# XmegaA4U_v2_0.net
KiCad netlist of a schematic drawn in EAGLE
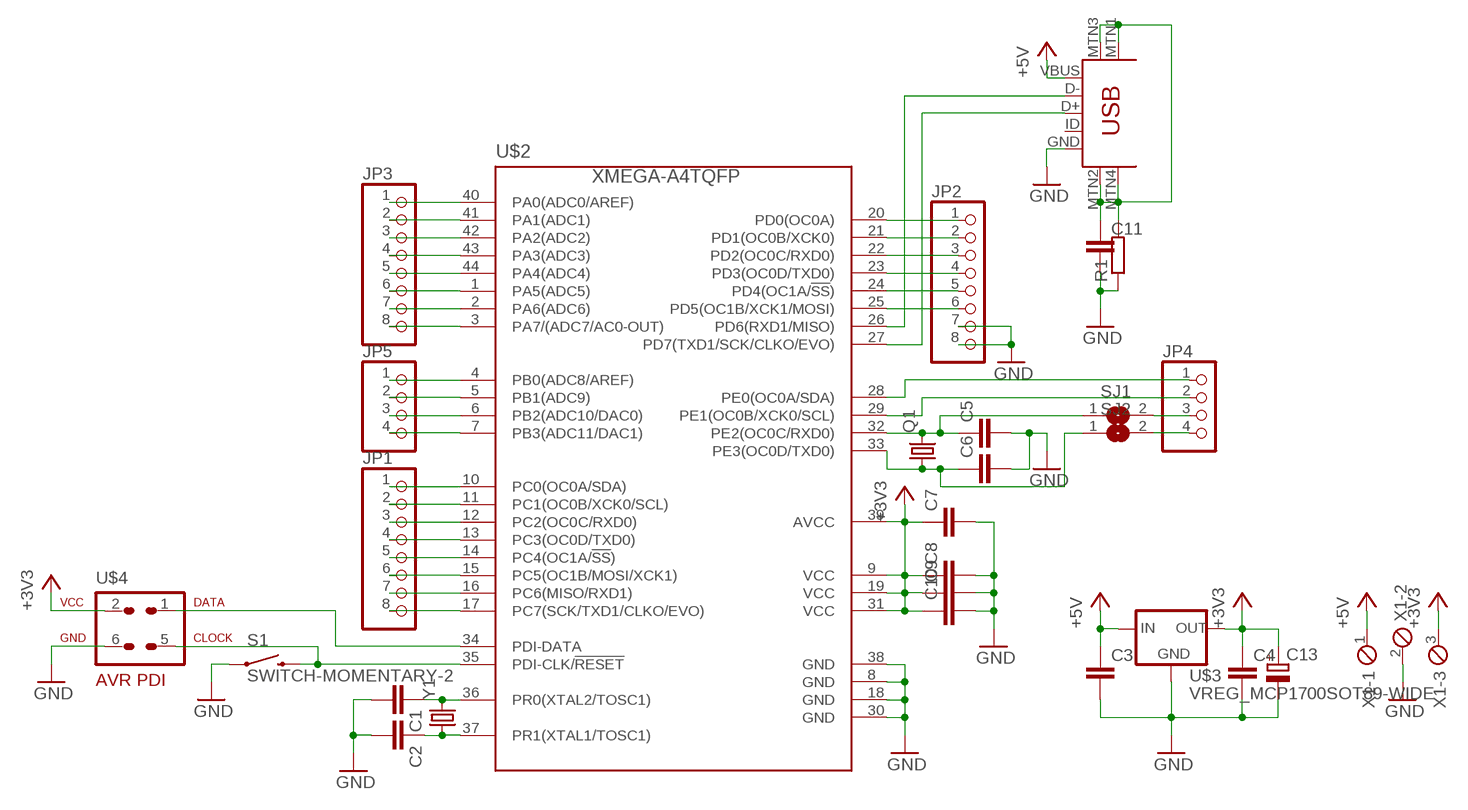
[diagram p0: schematic, sheet 1]

(export (version "E")
  (design (tool "Eeschema 10.0.6"))
  (components
    (comp (ref "C1")
      (value "C-EUC0603")
      (footprint "eagle-import:C0603")
      (libsource (lib "eagle-import") (part "C-EUC0603"))
    )
    (comp (ref "C2")
      (value "C-EUC0603")
      (footprint "eagle-import:C0603")
      (libsource (lib "eagle-import") (part "C-EUC0603"))
    )
    (comp (ref "C3")
      (value "C-EUC0805")
      (footprint "eagle-import:C0805")
      (libsource (lib "eagle-import") (part "C-EUC0805"))
    )
    (comp (ref "C4")
      (value "C-EUC0603")
      (footprint "eagle-import:C0603")
      (libsource (lib "eagle-import") (part "C-EUC0603"))
    )
    (comp (ref "C5")
      (value "C-EUC0603")
      (footprint "eagle-import:C0603")
      (libsource (lib "eagle-import") (part "C-EUC0603"))
    )
    (comp (ref "C6")
      (value "C-EUC0603")
      (footprint "eagle-import:C0603")
      (libsource (lib "eagle-import") (part "C-EUC0603"))
    )
    (comp (ref "C7")
      (value "C-EUC0603")
      (footprint "eagle-import:C0603")
      (libsource (lib "eagle-import") (part "C-EUC0603"))
    )
    (comp (ref "C8")
      (value "C-EUC0603")
      (footprint "eagle-import:C0603")
      (libsource (lib "eagle-import") (part "C-EUC0603"))
    )
    (comp (ref "C9")
      (value "C-EUC0603")
      (footprint "eagle-import:C0603")
      (libsource (lib "eagle-import") (part "C-EUC0603"))
    )
    (comp (ref "C10")
      (value "C-EUC0603")
      (footprint "eagle-import:C0603")
      (libsource (lib "eagle-import") (part "C-EUC0603"))
    )
    (comp (ref "C11")
      (value "C-EUC0603")
      (footprint "eagle-import:C0603")
      (libsource (lib "eagle-import") (part "C-EUC0603"))
    )
    (comp (ref "C13")
      (value "CPOL-EUSMCA")
      (footprint "eagle-import:SMC_A")
      (libsource (lib "eagle-import") (part "CPOL-EUSMCA"))
    )
    (comp (ref "JP1")
      (value "PINHD_FIXEDPAD_ROUND-1X8")
      (footprint "eagle-import:1X08_ROUND")
      (libsource (lib "eagle-import") (part "PINHD_FIXEDPAD_ROUND-1X8"))
    )
    (comp (ref "JP2")
      (value "PINHD_FIXEDPAD_ROUND-1X8")
      (footprint "eagle-import:1X08_ROUND")
      (libsource (lib "eagle-import") (part "PINHD_FIXEDPAD_ROUND-1X8"))
    )
    (comp (ref "JP3")
      (value "PINHD_FIXEDPAD_ROUND-1X8")
      (footprint "eagle-import:1X08_ROUND")
      (libsource (lib "eagle-import") (part "PINHD_FIXEDPAD_ROUND-1X8"))
    )
    (comp (ref "JP4")
      (value "PINHD_FIXEDPAD_ROUND-1X4")
      (footprint "eagle-import:1X04_ROUND")
      (libsource (lib "eagle-import") (part "PINHD_FIXEDPAD_ROUND-1X4"))
    )
    (comp (ref "JP5")
      (value "PINHD_FIXEDPAD_ROUND-1X4")
      (footprint "eagle-import:1X04_ROUND")
      (libsource (lib "eagle-import") (part "PINHD_FIXEDPAD_ROUND-1X4"))
    )
    (comp (ref "Q1")
      (value "CRYSTALTC26V")
      (footprint "eagle-import:TC26V")
      (libsource (lib "eagle-import") (part "CRYSTALTC26V"))
    )
    (comp (ref "R1")
      (value "R-EU_R0603")
      (footprint "eagle-import:R0603")
      (libsource (lib "eagle-import") (part "R-EU_R0603"))
    )
    (comp (ref "S1")
      (value "SWITCH-MOMENTARY-2")
      (footprint "eagle-import:TACTILE_SWITCH_TALL")
      (libsource (lib "eagle-import") (part "SWITCH-MOMENTARY-2"))
    )
    (comp (ref "SJ1")
      (value "SJ_SMALL")
      (footprint "eagle-import:SJ_2S-NO")
      (libsource (lib "eagle-import") (part "SJ_SMALL"))
    )
    (comp (ref "SJ2")
      (value "SJ_SMALL")
      (footprint "eagle-import:SJ_2S-NO")
      (libsource (lib "eagle-import") (part "SJ_SMALL"))
    )
    (comp (ref "U$1")
      (value "USB-MINIB-5PIN")
      (footprint "eagle-import:USB-MINIB")
      (libsource (lib "eagle-import") (part "USB-MINIB-5PIN"))
    )
    (comp (ref "U$2")
      (value "XMEGA-A4TQFP")
      (footprint "eagle-import:TQFP44")
      (libsource (lib "eagle-import") (part "XMEGA-A4TQFP"))
    )
    (comp (ref "U$3")
      (value "VREG_MCP1700SOT89-WIDE")
      (footprint "eagle-import:SOT89-W")
      (libsource (lib "eagle-import") (part "VREG_MCP1700SOT89-WIDE"))
    )
    (comp (ref "U$4")
      (value "AVR-PDIVERT")
      (footprint "eagle-import:AVR-ISP-6")
      (libsource (lib "eagle-import") (part "AVR-PDIVERT"))
    )
    (comp (ref "X1")
      (value "MPT3")
      (footprint "eagle-import:3POL254")
      (libsource (lib "eagle-import") (part "MPT3"))
    )
    (comp (ref "Y1")
      (value "CRYSTAL5X3")
      (footprint "eagle-import:CRYSTAL-SMD-5X3")
      (libsource (lib "eagle-import") (part "CRYSTAL5X3"))
    )
  )
  (nets
    (net (code "1") (name "+3V3") (class "Default")
      (node (ref "C10") (pin "1") (pinfunction "1_1") (pintype "passive"))
      (node (ref "C13") (pin "+") (pinfunction "+_+") (pintype "passive"))
      (node (ref "C4") (pin "1") (pinfunction "1_1") (pintype "passive"))
      (node (ref "C7") (pin "1") (pinfunction "1_1") (pintype "passive"))
      (node (ref "C8") (pin "1") (pinfunction "1_1") (pintype "passive"))
      (node (ref "C9") (pin "1") (pinfunction "1_1") (pintype "passive"))
      (node (ref "U$2") (pin "19") (pinfunction "VCC_19") (pintype "power_in"))
      (node (ref "U$2") (pin "31") (pinfunction "VCC_31") (pintype "power_in"))
      (node (ref "U$2") (pin "39") (pinfunction "AVCC_39") (pintype "power_in"))
      (node (ref "U$2") (pin "9") (pinfunction "VCC_9") (pintype "power_in"))
      (node (ref "U$3") (pin "3") (pinfunction "OUT_3") (pintype "output"))
      (node (ref "U$4") (pin "2") (pinfunction "2_2") (pintype "passive"))
      (node (ref "X1") (pin "3") (pinfunction "1_3") (pintype "passive"))
    )
    (net (code "2") (name "+5V") (class "Default")
      (node (ref "C3") (pin "1") (pinfunction "1_1") (pintype "passive"))
      (node (ref "U$1") (pin "VBUS") (pinfunction "VBUS_VBUS") (pintype "bidirectional"))
      (node (ref "U$3") (pin "2") (pinfunction "IN_2") (pintype "input"))
      (node (ref "U$3") (pin "TAB") (pinfunction "IN_TAB") (pintype "input"))
      (node (ref "X1") (pin "1") (pinfunction "1_1") (pintype "passive"))
    )
    (net (code "3") (name "GND") (class "Default")
      (node (ref "C1") (pin "2") (pinfunction "2_2") (pintype "passive"))
      (node (ref "C10") (pin "2") (pinfunction "2_2") (pintype "passive"))
      (node (ref "C11") (pin "2") (pinfunction "2_2") (pintype "passive"))
      (node (ref "C13") (pin "-") (pinfunction "-_-") (pintype "passive"))
      (node (ref "C2") (pin "2") (pinfunction "2_2") (pintype "passive"))
      (node (ref "C3") (pin "2") (pinfunction "2_2") (pintype "passive"))
      (node (ref "C4") (pin "2") (pinfunction "2_2") (pintype "passive"))
      (node (ref "C5") (pin "2") (pinfunction "2_2") (pintype "passive"))
      (node (ref "C6") (pin "2") (pinfunction "2_2") (pintype "passive"))
      (node (ref "C7") (pin "2") (pinfunction "2_2") (pintype "passive"))
      (node (ref "C8") (pin "2") (pinfunction "2_2") (pintype "passive"))
      (node (ref "C9") (pin "2") (pinfunction "2_2") (pintype "passive"))
      (node (ref "JP2") (pin "7") (pinfunction "7_7") (pintype "passive"))
      (node (ref "JP2") (pin "8") (pinfunction "8_8") (pintype "passive"))
      (node (ref "R1") (pin "1") (pinfunction "1_1") (pintype "passive"))
      (node (ref "S1") (pin "A2") (pinfunction "1_A2") (pintype "passive"))
      (node (ref "U$1") (pin "GND") (pinfunction "GND_GND") (pintype "bidirectional"))
      (node (ref "U$2") (pin "18") (pinfunction "GND_18") (pintype "power_in"))
      (node (ref "U$2") (pin "30") (pinfunction "GND_30") (pintype "power_in"))
      (node (ref "U$2") (pin "38") (pinfunction "GND_38") (pintype "power_in"))
      (node (ref "U$2") (pin "8") (pinfunction "GND_8") (pintype "power_in"))
      (node (ref "U$3") (pin "1") (pinfunction "GND_1") (pintype "input"))
      (node (ref "U$4") (pin "6") (pinfunction "6_6") (pintype "passive"))
      (node (ref "X1") (pin "2") (pinfunction "1_2") (pintype "passive"))
    )
    (net (code "4") (name "Net-(JP4-Pad3)") (class "Default")
      (node (ref "JP4") (pin "3") (pinfunction "3_3") (pintype "passive"))
      (node (ref "SJ1") (pin "2") (pinfunction "2_2") (pintype "passive"))
    )
    (net (code "5") (name "Net-(JP4-Pad4)") (class "Default")
      (node (ref "JP4") (pin "4") (pinfunction "4_4") (pintype "passive"))
      (node (ref "SJ2") (pin "2") (pinfunction "2_2") (pintype "passive"))
    )
    (net (code "6") (name "Net-(S1-2)") (class "Default")
      (node (ref "S1") (pin "B2") (pinfunction "2_B2") (pintype "passive"))
      (node (ref "U$2") (pin "35") (pinfunction "PDI-CLK/~{RESET}_35") (pintype "input"))
      (node (ref "U$4") (pin "5") (pinfunction "5_5") (pintype "passive"))
    )
    (net (code "7") (name "Net-(U$1-MTN1)") (class "Default")
      (node (ref "C11") (pin "1") (pinfunction "1_1") (pintype "passive"))
      (node (ref "R1") (pin "2") (pinfunction "2_2") (pintype "passive"))
      (node (ref "U$1") (pin "MTN1") (pinfunction "MTN2_MTN1") (pintype "bidirectional"))
      (node (ref "U$1") (pin "MTN2") (pinfunction "MTN3_MTN2") (pintype "bidirectional"))
      (node (ref "U$1") (pin "MTN3") (pinfunction "MTN1_MTN3") (pintype "bidirectional"))
      (node (ref "U$1") (pin "MTN4") (pinfunction "MTN4_MTN4") (pintype "bidirectional"))
    )
    (net (code "8") (name "Net-(U$2-PA0(ADC0{slash}AREF))") (class "Default")
      (node (ref "JP3") (pin "1") (pinfunction "1_1") (pintype "passive"))
      (node (ref "U$2") (pin "40") (pinfunction "PA0(ADC0/AREF)_40") (pintype "bidirectional"))
    )
    (net (code "9") (name "Net-(U$2-PA1(ADC1))") (class "Default")
      (node (ref "JP3") (pin "2") (pinfunction "2_2") (pintype "passive"))
      (node (ref "U$2") (pin "41") (pinfunction "PA1(ADC1)_41") (pintype "bidirectional"))
    )
    (net (code "10") (name "Net-(U$2-PA2(ADC2))") (class "Default")
      (node (ref "JP3") (pin "3") (pinfunction "3_3") (pintype "passive"))
      (node (ref "U$2") (pin "42") (pinfunction "PA2(ADC2)_42") (pintype "bidirectional"))
    )
    (net (code "11") (name "Net-(U$2-PA3(ADC3))") (class "Default")
      (node (ref "JP3") (pin "4") (pinfunction "4_4") (pintype "passive"))
      (node (ref "U$2") (pin "43") (pinfunction "PA3(ADC3)_43") (pintype "bidirectional"))
    )
    (net (code "12") (name "Net-(U$2-PA4(ADC4))") (class "Default")
      (node (ref "JP3") (pin "5") (pinfunction "5_5") (pintype "passive"))
      (node (ref "U$2") (pin "44") (pinfunction "PA4(ADC4)_44") (pintype "bidirectional"))
    )
    (net (code "13") (name "Net-(U$2-PA5(ADC5))") (class "Default")
      (node (ref "JP3") (pin "6") (pinfunction "6_6") (pintype "passive"))
      (node (ref "U$2") (pin "1") (pinfunction "PA5(ADC5)_1") (pintype "bidirectional"))
    )
    (net (code "14") (name "Net-(U$2-PA6(ADC6))") (class "Default")
      (node (ref "JP3") (pin "7") (pinfunction "7_7") (pintype "passive"))
      (node (ref "U$2") (pin "2") (pinfunction "PA6(ADC6)_2") (pintype "bidirectional"))
    )
    (net (code "15") (name "Net-(U$2-PA7{slash}(ADC7{slash}AC0-OUT))") (class "Default")
      (node (ref "JP3") (pin "8") (pinfunction "8_8") (pintype "passive"))
      (node (ref "U$2") (pin "3") (pinfunction "PA7/(ADC7/AC0-OUT)_3") (pintype "bidirectional"))
    )
    (net (code "16") (name "Net-(U$2-PB0(ADC8{slash}AREF))") (class "Default")
      (node (ref "JP5") (pin "1") (pinfunction "1_1") (pintype "passive"))
      (node (ref "U$2") (pin "4") (pinfunction "PB0(ADC8/AREF)_4") (pintype "bidirectional"))
    )
    (net (code "17") (name "Net-(U$2-PB1(ADC9))") (class "Default")
      (node (ref "JP5") (pin "2") (pinfunction "2_2") (pintype "passive"))
      (node (ref "U$2") (pin "5") (pinfunction "PB1(ADC9)_5") (pintype "bidirectional"))
    )
    (net (code "18") (name "Net-(U$2-PB2(ADC10{slash}DAC0))") (class "Default")
      (node (ref "JP5") (pin "3") (pinfunction "3_3") (pintype "passive"))
      (node (ref "U$2") (pin "6") (pinfunction "PB2(ADC10/DAC0)_6") (pintype "bidirectional"))
    )
    (net (code "19") (name "Net-(U$2-PB3(ADC11{slash}DAC1))") (class "Default")
      (node (ref "JP5") (pin "4") (pinfunction "4_4") (pintype "passive"))
      (node (ref "U$2") (pin "7") (pinfunction "PB3(ADC11/DAC1)_7") (pintype "bidirectional"))
    )
    (net (code "20") (name "Net-(U$2-PC0(OC0A{slash}SDA))") (class "Default")
      (node (ref "JP1") (pin "1") (pinfunction "1_1") (pintype "passive"))
      (node (ref "U$2") (pin "10") (pinfunction "PC0(OC0A/SDA)_10") (pintype "bidirectional"))
    )
    (net (code "21") (name "Net-(U$2-PC1(OC0B{slash}XCK0{slash}SCL))") (class "Default")
      (node (ref "JP1") (pin "2") (pinfunction "2_2") (pintype "passive"))
      (node (ref "U$2") (pin "11") (pinfunction "PC1(OC0B/XCK0/SCL)_11") (pintype "bidirectional"))
    )
    (net (code "22") (name "Net-(U$2-PC2(OC0C{slash}RXD0))") (class "Default")
      (node (ref "JP1") (pin "3") (pinfunction "3_3") (pintype "passive"))
      (node (ref "U$2") (pin "12") (pinfunction "PC2(OC0C/RXD0)_12") (pintype "bidirectional"))
    )
    (net (code "23") (name "Net-(U$2-PC3(OC0D{slash}TXD0))") (class "Default")
      (node (ref "JP1") (pin "4") (pinfunction "4_4") (pintype "passive"))
      (node (ref "U$2") (pin "13") (pinfunction "PC3(OC0D/TXD0)_13") (pintype "bidirectional"))
    )
    (net (code "24") (name "Net-(U$2-PC4(OC1A{slash}~{SS}))") (class "Default")
      (node (ref "JP1") (pin "5") (pinfunction "5_5") (pintype "passive"))
      (node (ref "U$2") (pin "14") (pinfunction "PC4(OC1A/~{SS})_14") (pintype "bidirectional"))
    )
    (net (code "25") (name "Net-(U$2-PC5(OC1B{slash}MOSI{slash}XCK1))") (class "Default")
      (node (ref "JP1") (pin "6") (pinfunction "6_6") (pintype "passive"))
      (node (ref "U$2") (pin "15") (pinfunction "PC5(OC1B/MOSI/XCK1)_15") (pintype "bidirectional"))
    )
    (net (code "26") (name "Net-(U$2-PC6(MISO{slash}RXD1))") (class "Default")
      (node (ref "JP1") (pin "7") (pinfunction "7_7") (pintype "passive"))
      (node (ref "U$2") (pin "16") (pinfunction "PC6(MISO/RXD1)_16") (pintype "bidirectional"))
    )
    (net (code "27") (name "Net-(U$2-PC7(SCK{slash}TXD1{slash}CLKO{slash}EVO))") (class "Default")
      (node (ref "JP1") (pin "8") (pinfunction "8_8") (pintype "passive"))
      (node (ref "U$2") (pin "17") (pinfunction "PC7(SCK/TXD1/CLKO/EVO)_17") (pintype "bidirectional"))
    )
    (net (code "28") (name "Net-(U$2-PD0(OC0A))") (class "Default")
      (node (ref "JP2") (pin "1") (pinfunction "1_1") (pintype "passive"))
      (node (ref "U$2") (pin "20") (pinfunction "PD0(OC0A)_20") (pintype "bidirectional"))
    )
    (net (code "29") (name "Net-(U$2-PD1(OC0B{slash}XCK0))") (class "Default")
      (node (ref "JP2") (pin "2") (pinfunction "2_2") (pintype "passive"))
      (node (ref "U$2") (pin "21") (pinfunction "PD1(OC0B/XCK0)_21") (pintype "bidirectional"))
    )
    (net (code "30") (name "Net-(U$2-PD2(OC0C{slash}RXD0))") (class "Default")
      (node (ref "JP2") (pin "3") (pinfunction "3_3") (pintype "passive"))
      (node (ref "U$2") (pin "22") (pinfunction "PD2(OC0C/RXD0)_22") (pintype "bidirectional"))
    )
    (net (code "31") (name "Net-(U$2-PD3(OC0D{slash}TXD0))") (class "Default")
      (node (ref "JP2") (pin "4") (pinfunction "4_4") (pintype "passive"))
      (node (ref "U$2") (pin "23") (pinfunction "PD3(OC0D/TXD0)_23") (pintype "bidirectional"))
    )
    (net (code "32") (name "Net-(U$2-PD4(OC1A{slash}~{SS}))") (class "Default")
      (node (ref "JP2") (pin "5") (pinfunction "5_5") (pintype "passive"))
      (node (ref "U$2") (pin "24") (pinfunction "PD4(OC1A/~{SS})_24") (pintype "bidirectional"))
    )
    (net (code "33") (name "Net-(U$2-PD5(OC1B{slash}XCK1{slash}MOSI))") (class "Default")
      (node (ref "JP2") (pin "6") (pinfunction "6_6") (pintype "passive"))
      (node (ref "U$2") (pin "25") (pinfunction "PD5(OC1B/XCK1/MOSI)_25") (pintype "bidirectional"))
    )
    (net (code "34") (name "Net-(U$2-PD6(RXD1{slash}MISO))") (class "Default")
      (node (ref "U$1") (pin "D-") (pinfunction "D-_D-") (pintype "bidirectional"))
      (node (ref "U$2") (pin "26") (pinfunction "PD6(RXD1/MISO)_26") (pintype "bidirectional"))
    )
    (net (code "35") (name "Net-(U$2-PD7(TXD1{slash}SCK{slash}CLKO{slash}EVO))") (class "Default")
      (node (ref "U$1") (pin "D+") (pinfunction "D+_D+") (pintype "bidirectional"))
      (node (ref "U$2") (pin "27") (pinfunction "PD7(TXD1/SCK/CLKO/EVO)_27") (pintype "bidirectional"))
    )
    (net (code "36") (name "Net-(U$2-PDI-DATA)") (class "Default")
      (node (ref "U$2") (pin "34") (pinfunction "PDI-DATA_34") (pintype "bidirectional"))
      (node (ref "U$4") (pin "1") (pinfunction "1_1") (pintype "passive"))
    )
    (net (code "37") (name "Net-(U$2-PE0(OC0A{slash}SDA))") (class "Default")
      (node (ref "JP4") (pin "1") (pinfunction "1_1") (pintype "passive"))
      (node (ref "U$2") (pin "28") (pinfunction "PE0(OC0A/SDA)_28") (pintype "bidirectional"))
    )
    (net (code "38") (name "Net-(U$2-PE1(OC0B{slash}XCK0{slash}SCL))") (class "Default")
      (node (ref "JP4") (pin "2") (pinfunction "2_2") (pintype "passive"))
      (node (ref "U$2") (pin "29") (pinfunction "PE1(OC0B/XCK0/SCL)_29") (pintype "bidirectional"))
    )
    (net (code "39") (name "Net-(U$2-PE2(OC0C{slash}RXD0))") (class "Default")
      (node (ref "C5") (pin "1") (pinfunction "1_1") (pintype "passive"))
      (node (ref "Q1") (pin "2") (pinfunction "2_2") (pintype "passive"))
      (node (ref "SJ1") (pin "1") (pinfunction "1_1") (pintype "passive"))
      (node (ref "U$2") (pin "32") (pinfunction "PE2(OC0C/RXD0)_32") (pintype "bidirectional"))
    )
    (net (code "40") (name "Net-(U$2-PE3(OC0D{slash}TXD0))") (class "Default")
      (node (ref "C6") (pin "1") (pinfunction "1_1") (pintype "passive"))
      (node (ref "Q1") (pin "1") (pinfunction "1_1") (pintype "passive"))
      (node (ref "SJ2") (pin "1") (pinfunction "1_1") (pintype "passive"))
      (node (ref "U$2") (pin "33") (pinfunction "PE3(OC0D/TXD0)_33") (pintype "bidirectional"))
    )
    (net (code "41") (name "Net-(U$2-PR0(XTAL2{slash}TOSC1))") (class "Default")
      (node (ref "C1") (pin "1") (pinfunction "1_1") (pintype "passive"))
      (node (ref "U$2") (pin "36") (pinfunction "PR0(XTAL2/TOSC1)_36") (pintype "bidirectional"))
      (node (ref "Y1") (pin "3") (pinfunction "2_3") (pintype "passive"))
    )
    (net (code "42") (name "Net-(U$2-PR1(XTAL1{slash}TOSC1))") (class "Default")
      (node (ref "C2") (pin "1") (pinfunction "1_1") (pintype "passive"))
      (node (ref "U$2") (pin "37") (pinfunction "PR1(XTAL1/TOSC1)_37") (pintype "bidirectional"))
      (node (ref "Y1") (pin "1") (pinfunction "1_1") (pintype "passive"))
    )
    (net (code "43") (name "unconnected-(U$1-PadID)") (class "Default")
      (node (ref "U$1") (pin "ID") (pinfunction "ID_ID") (pintype "bidirectional"))
    )
  )
)
